# Bridge.net
KiCad netlist of a schematic drawn in Altium Designer
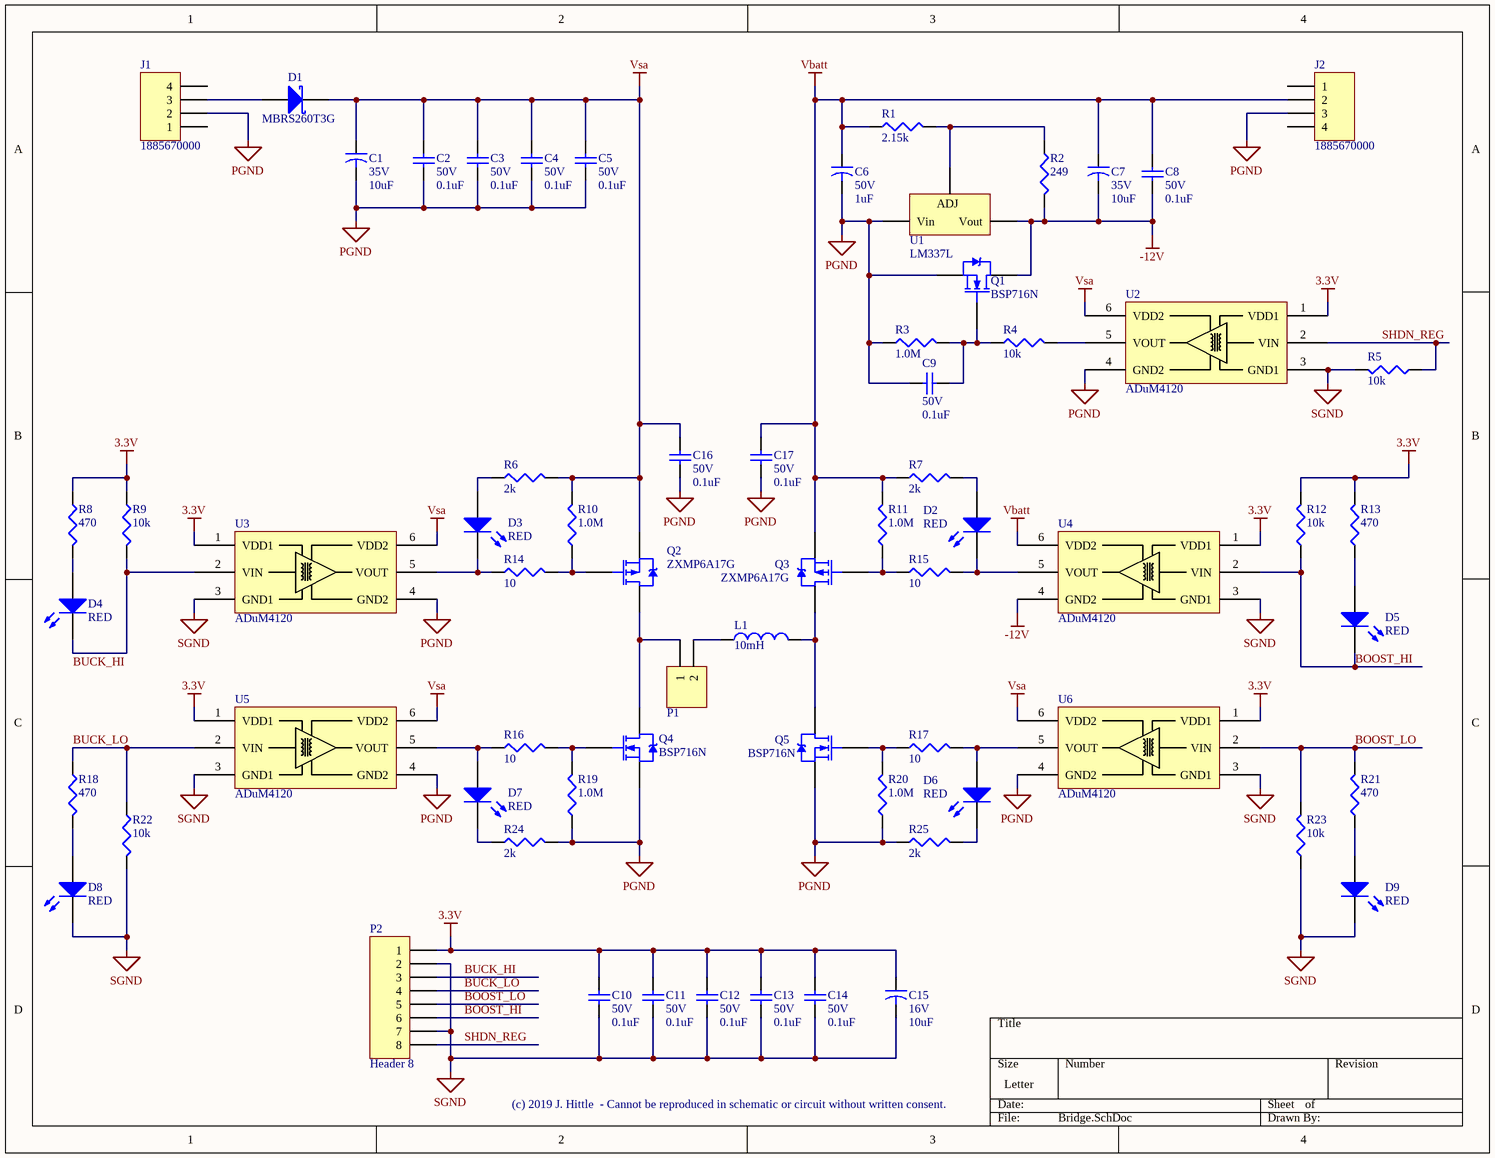
[diagram p0: Bridge.SchDoc]

(export (version "E")
  (design (tool "Eeschema 10.0.6"))
  (components
    (comp (ref "C1")
      (value "10uF")
      (footprint "C2312 Tantalum")
      (description "Capacitor, 600mohm, 200mA@100kHz")
      (fields
        (field (name "PART NUMBER") "TRJC106K035R0600")
        (field (name "VOLTAGE") "35V")
        (field (name "Comment") "Cap Polarized")
      )
      (libsource (lib "Generic Devices") (part "Cap Polarized"))
    )
    (comp (ref "C2")
      (value "0.1uF")
      (footprint "C0805")
      (description "Capacitor")
      (fields
        (field (name "PART NUMBER") "CL21B104KBCNNNC")
        (field (name "VOLTAGE") "50V")
        (field (name "Comment") "Cap Chip")
      )
      (libsource (lib "Generic Devices") (part "Cap Chip"))
    )
    (comp (ref "C3")
      (value "0.1uF")
      (footprint "C0805")
      (description "Capacitor")
      (fields
        (field (name "PART NUMBER") "CL21B104KBCNNNC")
        (field (name "VOLTAGE") "50V")
        (field (name "Comment") "Cap Chip")
      )
      (libsource (lib "Generic Devices") (part "Cap Chip"))
    )
    (comp (ref "C4")
      (value "0.1uF")
      (footprint "C0805")
      (description "Capacitor")
      (fields
        (field (name "PART NUMBER") "CL21B104KBCNNNC")
        (field (name "VOLTAGE") "50V")
        (field (name "Comment") "Cap Chip")
      )
      (libsource (lib "Generic Devices") (part "Cap Chip"))
    )
    (comp (ref "C5")
      (value "0.1uF")
      (footprint "C0805")
      (description "Capacitor")
      (fields
        (field (name "PART NUMBER") "CL21B104KBCNNNC")
        (field (name "VOLTAGE") "50V")
        (field (name "Comment") "Cap Chip")
      )
      (libsource (lib "Generic Devices") (part "Cap Chip"))
    )
    (comp (ref "C6")
      (value "1uF")
      (footprint "C2312 Tantalum")
      (description "Capacitor, 600mohm, 200mA@100kHz")
      (fields
        (field (name "PART NUMBER") "TAJC105K050RNJ")
        (field (name "VOLTAGE") "50V")
        (field (name "Comment") "Cap Polarized")
      )
      (libsource (lib "Generic Devices") (part "Cap Polarized"))
    )
    (comp (ref "C7")
      (value "10uF")
      (footprint "C2312 Tantalum")
      (description "Capacitor, 600mohm, 200mA@100kHz")
      (fields
        (field (name "PART NUMBER") "TRJC106K035R0600")
        (field (name "VOLTAGE") "35V")
        (field (name "Comment") "Cap Polarized")
      )
      (libsource (lib "Generic Devices") (part "Cap Polarized"))
    )
    (comp (ref "C8")
      (value "0.1uF")
      (footprint "C0805")
      (description "Capacitor")
      (fields
        (field (name "PART NUMBER") "CL21B104KBCNNNC")
        (field (name "VOLTAGE") "50V")
        (field (name "Comment") "Cap Chip")
      )
      (libsource (lib "Generic Devices") (part "Cap Chip"))
    )
    (comp (ref "C9")
      (value "0.1uF")
      (footprint "C0603")
      (description "Capacitor")
      (fields
        (field (name "PART NUMBER") "CL10B104KB8NNNC")
        (field (name "VOLTAGE") "50V")
        (field (name "Comment") "Cap Chip")
      )
      (libsource (lib "Generic Devices") (part "Cap Chip"))
    )
    (comp (ref "C10")
      (value "0.1uF")
      (footprint "C0805")
      (description "Capacitor")
      (fields
        (field (name "PART NUMBER") "CL21B104KBCNNNC")
        (field (name "VOLTAGE") "50V")
        (field (name "Comment") "Cap Chip")
      )
      (libsource (lib "Generic Devices") (part "Cap Chip"))
    )
    (comp (ref "C11")
      (value "0.1uF")
      (footprint "C0805")
      (description "Capacitor")
      (fields
        (field (name "PART NUMBER") "CL21B104KBCNNNC")
        (field (name "VOLTAGE") "50V")
        (field (name "Comment") "Cap Chip")
      )
      (libsource (lib "Generic Devices") (part "Cap Chip"))
    )
    (comp (ref "C12")
      (value "0.1uF")
      (footprint "C0805")
      (description "Capacitor")
      (fields
        (field (name "PART NUMBER") "CL21B104KBCNNNC")
        (field (name "VOLTAGE") "50V")
        (field (name "Comment") "Cap Chip")
      )
      (libsource (lib "Generic Devices") (part "Cap Chip"))
    )
    (comp (ref "C13")
      (value "0.1uF")
      (footprint "C0805")
      (description "Capacitor")
      (fields
        (field (name "PART NUMBER") "CL21B104KBCNNNC")
        (field (name "VOLTAGE") "50V")
        (field (name "Comment") "Cap Chip")
      )
      (libsource (lib "Generic Devices") (part "Cap Chip"))
    )
    (comp (ref "C14")
      (value "0.1uF")
      (footprint "C0805")
      (description "Capacitor")
      (fields
        (field (name "PART NUMBER") "CL21B104KBCNNNC")
        (field (name "VOLTAGE") "50V")
        (field (name "Comment") "Cap Chip")
      )
      (libsource (lib "Generic Devices") (part "Cap Chip"))
    )
    (comp (ref "C15")
      (value "10uF")
      (footprint "C1206 Tantalum")
      (description "Capacitor, 600mohm, 200mA@100kHz")
      (fields
        (field (name "PART NUMBER") "TAJA106K016RNJV")
        (field (name "VOLTAGE") "16V")
        (field (name "Comment") "Cap Polarized")
      )
      (libsource (lib "Generic Devices") (part "Cap Polarized"))
    )
    (comp (ref "C16")
      (value "0.1uF")
      (footprint "C0603")
      (description "Capacitor")
      (fields
        (field (name "PART NUMBER") "CL10B104KB8NNNC")
        (field (name "VOLTAGE") "50V")
        (field (name "Comment") "Cap Chip")
      )
      (libsource (lib "Generic Devices") (part "Cap Chip"))
    )
    (comp (ref "C17")
      (value "0.1uF")
      (footprint "C0603")
      (description "Capacitor")
      (fields
        (field (name "PART NUMBER") "CL10B104KB8NNNC")
        (field (name "VOLTAGE") "50V")
        (field (name "Comment") "Cap Chip")
      )
      (libsource (lib "Generic Devices") (part "Cap Chip"))
    )
    (comp (ref "D1")
      (value "MBRS260T3G")
      (footprint "SMB")
      (description "Schottky Diode")
      (fields (field (name "PUBLISHER") "Altium Limited"))
      (libsource (lib "Miscellaneous Devices") (part "D Schottky"))
    )
    (comp (ref "D2")
      (value "RED")
      (footprint "Generic Devices:0603_LED_Red")
      (description "Red LED")
      (fields (field (name "PART NUMBER") "LTST-C193KRKT-5A") (field (name "PUBLISHER") "Altium Limited"))
      (libsource (lib "Miscellaneous Devices") (part "LED0"))
    )
    (comp (ref "D3")
      (value "RED")
      (footprint "Generic Devices:0603_LED_Red")
      (description "Red LED")
      (fields (field (name "PART NUMBER") "LTST-C193KRKT-5A") (field (name "PUBLISHER") "Altium Limited"))
      (libsource (lib "Miscellaneous Devices") (part "LED0"))
    )
    (comp (ref "D4")
      (value "RED")
      (footprint "Generic Devices:0603_LED_Red")
      (description "Red LED")
      (fields (field (name "PART NUMBER") "LTST-C193KRKT-5A") (field (name "PUBLISHER") "Altium Limited"))
      (libsource (lib "Miscellaneous Devices") (part "LED0"))
    )
    (comp (ref "D5")
      (value "RED")
      (footprint "Generic Devices:0603_LED_Red")
      (description "Red LED")
      (fields (field (name "PART NUMBER") "LTST-C193KRKT-5A") (field (name "PUBLISHER") "Altium Limited"))
      (libsource (lib "Miscellaneous Devices") (part "LED0"))
    )
    (comp (ref "D6")
      (value "RED")
      (footprint "Generic Devices:0603_LED_Red")
      (description "Red LED")
      (fields (field (name "PART NUMBER") "LTST-C193KRKT-5A") (field (name "PUBLISHER") "Altium Limited"))
      (libsource (lib "Miscellaneous Devices") (part "LED0"))
    )
    (comp (ref "D7")
      (value "RED")
      (footprint "Generic Devices:0603_LED_Red")
      (description "Red LED")
      (fields (field (name "PART NUMBER") "LTST-C193KRKT-5A") (field (name "PUBLISHER") "Altium Limited"))
      (libsource (lib "Miscellaneous Devices") (part "LED0"))
    )
    (comp (ref "D8")
      (value "RED")
      (footprint "Generic Devices:0603_LED_Red")
      (description "Red LED")
      (fields (field (name "PART NUMBER") "LTST-C193KRKT-5A") (field (name "PUBLISHER") "Altium Limited"))
      (libsource (lib "Miscellaneous Devices") (part "LED0"))
    )
    (comp (ref "D9")
      (value "RED")
      (footprint "Generic Devices:0603_LED_Red")
      (description "Red LED")
      (fields (field (name "PART NUMBER") "LTST-C193KRKT-5A") (field (name "PUBLISHER") "Altium Limited"))
      (libsource (lib "Miscellaneous Devices") (part "LED0"))
    )
    (comp (ref "J1")
      (value "1885670000")
      (footprint "1885670000")
      (description "TERM BLOCK 4POS 45DEG 3.5MM PCB")
      (fields (field (name "VOLTAGE") "300V"))
      (libsource (lib "") (part "1885670000_1"))
    )
    (comp (ref "J2")
      (value "1885670000")
      (footprint "1885670000")
      (description "TERM BLOCK 4POS 45DEG 3.5MM PCB")
      (fields (field (name "VOLTAGE") "300V"))
      (libsource (lib "Connectors") (part "1885670000"))
    )
    (comp (ref "L1")
      (value "10mH")
      (footprint "141060XC")
      (description "Inductor")
      (fields (field (name "PART NUMBER") "1410606C or 1410604C") (field (name "PUBLISHER") "Altium Limited"))
      (libsource (lib "Miscellaneous Devices") (part "Inductor"))
    )
    (comp (ref "P1")
      (value "~")
      (footprint "HDR1X2")
      (description "Header, 2-Pin, 100mil")
      (fields (field (name "PUBLISHER") "Altium Limited"))
      (libsource (lib "Connectors") (part "Header 2"))
    )
    (comp (ref "P2")
      (value "Header 8")
      (footprint "HDR1X8")
      (description "Header, 8-Pin, 100mil")
      (fields (field (name "PUBLISHER") "Altium Limited"))
      (libsource (lib "Miscellaneous Connectors") (part "Header 8"))
    )
    (comp (ref "Q1")
      (value "BSP716N")
      (footprint "SOT223")
      (description "N-Channel MOSFET")
      (fields (field (name "PART NUMBER") "BSP716NH6327XTSA1"))
      (libsource (lib "Generic Devices") (part "NMOS"))
    )
    (comp (ref "Q2")
      (value "ZXMP6A17G")
      (footprint "SOT223")
      (description "P-Channel MOSFET")
      (fields (field (name "PART NUMBER") "ZXMP6A17GTA"))
      (libsource (lib "Generic Devices") (part "PMOS"))
    )
    (comp (ref "Q3")
      (value "ZXMP6A17G")
      (footprint "SOT223")
      (description "P-Channel MOSFET")
      (fields (field (name "PART NUMBER") "ZXMP6A17GTA"))
      (libsource (lib "Generic Devices") (part "PMOS"))
    )
    (comp (ref "Q4")
      (value "BSP716N")
      (footprint "SOT223")
      (description "N-Channel MOSFET")
      (fields (field (name "PART NUMBER") "BSP716NH6327XTSA1"))
      (libsource (lib "Generic Devices") (part "NMOS"))
    )
    (comp (ref "Q5")
      (value "BSP716N")
      (footprint "SOT223")
      (description "N-Channel MOSFET")
      (fields (field (name "PART NUMBER") "BSP716NH6327XTSA1"))
      (libsource (lib "Generic Devices") (part "NMOS"))
    )
    (comp (ref "R1")
      (value "2.15k")
      (footprint "R0805")
      (description "Resistor")
      (fields (field (name "PART NUMBER") "RC0805FR-072K15L") (field (name "POWER") "0.125"))
      (libsource (lib "Generic Devices") (part "Resistor_Chip"))
    )
    (comp (ref "R2")
      (value "249")
      (footprint "R0603")
      (description "Resistor")
      (fields (field (name "PART NUMBER") "RC0603FR-07249RL") (field (name "POWER") "0.100"))
      (libsource (lib "Generic Devices") (part "Resistor_Chip"))
    )
    (comp (ref "R3")
      (value "1.0M")
      (footprint "R0603")
      (description "Resistor")
      (fields (field (name "PART NUMBER") "RC0603FR-071ML") (field (name "POWER") "0.100"))
      (libsource (lib "Generic Devices") (part "Resistor_Chip"))
    )
    (comp (ref "R4")
      (value "10k")
      (footprint "R0603")
      (description "Resistor")
      (fields (field (name "PART NUMBER") "RC0603FR-0710KL") (field (name "POWER") "0.100"))
      (libsource (lib "Generic Devices") (part "Resistor_Chip"))
    )
    (comp (ref "R5")
      (value "10k")
      (footprint "R0603")
      (description "Resistor")
      (fields (field (name "PART NUMBER") "RC0603FR-0710KL") (field (name "POWER") "0.100"))
      (libsource (lib "Generic Devices") (part "Resistor_Chip"))
    )
    (comp (ref "R6")
      (value "2k")
      (footprint "R0603")
      (description "Resistor")
      (fields (field (name "PART NUMBER") "RC0805FR-072KL") (field (name "POWER") "0.125"))
      (libsource (lib "Generic Devices") (part "Resistor_Chip"))
    )
    (comp (ref "R7")
      (value "2k")
      (footprint "R0603")
      (description "Resistor")
      (fields (field (name "PART NUMBER") "RC0805FR-072KL") (field (name "POWER") "0.125"))
      (libsource (lib "Generic Devices") (part "Resistor_Chip"))
    )
    (comp (ref "R8")
      (value "470")
      (footprint "R0603")
      (description "Resistor")
      (fields (field (name "PART NUMBER") "RC0603FR-07470RL") (field (name "POWER") "0.100"))
      (libsource (lib "Generic Devices") (part "Resistor_Chip"))
    )
    (comp (ref "R9")
      (value "10k")
      (footprint "R0603")
      (description "Resistor")
      (fields (field (name "PART NUMBER") "RC0603FR-0710KL") (field (name "POWER") "0.100"))
      (libsource (lib "Generic Devices") (part "Resistor_Chip"))
    )
    (comp (ref "R10")
      (value "1.0M")
      (footprint "R0603")
      (description "Resistor")
      (fields (field (name "PART NUMBER") "RC0603FR-071ML") (field (name "POWER") "0.100"))
      (libsource (lib "Generic Devices") (part "Resistor_Chip"))
    )
    (comp (ref "R11")
      (value "1.0M")
      (footprint "R0603")
      (description "Resistor")
      (fields (field (name "PART NUMBER") "RC0603FR-071ML") (field (name "POWER") "0.100"))
      (libsource (lib "Generic Devices") (part "Resistor_Chip"))
    )
    (comp (ref "R12")
      (value "10k")
      (footprint "R0603")
      (description "Resistor")
      (fields (field (name "PART NUMBER") "RC0603FR-0710KL") (field (name "POWER") "0.100"))
      (libsource (lib "Generic Devices") (part "Resistor_Chip"))
    )
    (comp (ref "R13")
      (value "470")
      (footprint "R0603")
      (description "Resistor")
      (fields (field (name "PART NUMBER") "RC0603FR-07470RL") (field (name "POWER") "0.100"))
      (libsource (lib "Generic Devices") (part "Resistor_Chip"))
    )
    (comp (ref "R14")
      (value "10")
      (footprint "R1206")
      (description "Resistor")
      (fields (field (name "PART NUMBER") "RC1206FR-0710RL") (field (name "POWER") "0.250"))
      (libsource (lib "Generic Devices") (part "Resistor_Chip"))
    )
    (comp (ref "R15")
      (value "10")
      (footprint "R1206")
      (description "Resistor")
      (fields (field (name "PART NUMBER") "RC1206FR-0710RL") (field (name "POWER") "0.250"))
      (libsource (lib "Generic Devices") (part "Resistor_Chip"))
    )
    (comp (ref "R16")
      (value "10")
      (footprint "R1206")
      (description "Resistor")
      (fields (field (name "PART NUMBER") "RC1206FR-0710RL") (field (name "POWER") "0.250"))
      (libsource (lib "Generic Devices") (part "Resistor_Chip"))
    )
    (comp (ref "R17")
      (value "10")
      (footprint "R1206")
      (description "Resistor")
      (fields (field (name "PART NUMBER") "RC1206FR-0710RL") (field (name "POWER") "0.250"))
      (libsource (lib "Generic Devices") (part "Resistor_Chip"))
    )
    (comp (ref "R18")
      (value "470")
      (footprint "R0603")
      (description "Resistor")
      (fields (field (name "PART NUMBER") "RC0603FR-07470RL") (field (name "POWER") "0.100"))
      (libsource (lib "Generic Devices") (part "Resistor_Chip"))
    )
    (comp (ref "R19")
      (value "1.0M")
      (footprint "R0603")
      (description "Resistor")
      (fields (field (name "PART NUMBER") "RC0603FR-071ML") (field (name "POWER") "0.100"))
      (libsource (lib "Generic Devices") (part "Resistor_Chip"))
    )
    (comp (ref "R20")
      (value "1.0M")
      (footprint "R0603")
      (description "Resistor")
      (fields (field (name "PART NUMBER") "RC0603FR-071ML") (field (name "POWER") "0.100"))
      (libsource (lib "Generic Devices") (part "Resistor_Chip"))
    )
    (comp (ref "R21")
      (value "470")
      (footprint "R0603")
      (description "Resistor")
      (fields (field (name "PART NUMBER") "RC0603FR-07470RL") (field (name "POWER") "0.100"))
      (libsource (lib "Generic Devices") (part "Resistor_Chip"))
    )
    (comp (ref "R22")
      (value "10k")
      (footprint "R0603")
      (description "Resistor")
      (fields (field (name "PART NUMBER") "RC0603FR-0710KL") (field (name "POWER") "0.100"))
      (libsource (lib "Generic Devices") (part "Resistor_Chip"))
    )
    (comp (ref "R23")
      (value "10k")
      (footprint "R0603")
      (description "Resistor")
      (fields (field (name "PART NUMBER") "RC0603FR-0710KL") (field (name "POWER") "0.100"))
      (libsource (lib "Generic Devices") (part "Resistor_Chip"))
    )
    (comp (ref "R24")
      (value "2k")
      (footprint "R0603")
      (description "Resistor")
      (fields (field (name "PART NUMBER") "RC0805FR-072KL") (field (name "POWER") "0.125"))
      (libsource (lib "Generic Devices") (part "Resistor_Chip"))
    )
    (comp (ref "R25")
      (value "2k")
      (footprint "R0603")
      (description "Resistor")
      (fields (field (name "PART NUMBER") "RC0805FR-072KL") (field (name "POWER") "0.125"))
      (libsource (lib "Generic Devices") (part "Resistor_Chip"))
    )
    (comp (ref "U1")
      (value "LM337L")
      (footprint "TO-92A")
      (description "Negative Voltage Regulator")
      (fields (field (name "PART NUMBER") "LM337LZ/NOPB"))
      (libsource (lib "Generic Devices") (part "Neg Volt Reg - Adj"))
    )
    (comp (ref "U2")
      (value "ADuM4120")
      (footprint "SOIC RI-6-1")
      (description "Isolated Gate-Driver")
      (fields (field (name "PART NUMBER") "ADuM4120-1ARIZ"))
      (libsource (lib "Specific Devices") (part "ADuM4120"))
    )
    (comp (ref "U3")
      (value "ADuM4120")
      (footprint "SOIC RI-6-1")
      (description "Isolated Gate-Driver")
      (fields (field (name "PART NUMBER") "ADuM4120-1ARIZ"))
      (libsource (lib "") (part "ADuM4120_1"))
    )
    (comp (ref "U4")
      (value "ADuM4120")
      (footprint "SOIC RI-6-1")
      (description "Isolated Gate-Driver")
      (fields (field (name "PART NUMBER") "ADuM4120-1ARIZ"))
      (libsource (lib "Specific Devices") (part "ADuM4120"))
    )
    (comp (ref "U5")
      (value "ADuM4120")
      (footprint "SOIC RI-6-1")
      (description "Isolated Gate-Driver")
      (fields (field (name "PART NUMBER") "ADuM4120-1ARIZ"))
      (libsource (lib "") (part "ADuM4120_1"))
    )
    (comp (ref "U6")
      (value "ADuM4120")
      (footprint "SOIC RI-6-1")
      (description "Isolated Gate-Driver")
      (fields (field (name "PART NUMBER") "ADuM4120-1ARIZ"))
      (libsource (lib "Specific Devices") (part "ADuM4120"))
    )
  )
  (nets
    (net (code "1") (name "-12V") (class "Default")
      (node (ref "C7") (pin "2") (pinfunction "2_2") (pintype "passive"))
      (node (ref "C8") (pin "1") (pinfunction "1_1") (pintype "passive"))
      (node (ref "Q1") (pin "D") (pinfunction "D_D") (pintype "passive"))
      (node (ref "R2") (pin "2") (pinfunction "2_2") (pintype "passive"))
      (node (ref "U1") (pin "Vout") (pinfunction "Vout_Vout") (pintype "passive"))
      (node (ref "U4") (pin "4") (pinfunction "GND2_4") (pintype "passive"))
    )
    (net (code "2") (name "/BOOST_HI") (class "Default")
      (node (ref "D5") (pin "2") (pinfunction "K_2") (pintype "passive"))
      (node (ref "P2") (pin "6") (pinfunction "6_6") (pintype "passive"))
      (node (ref "R12") (pin "1") (pinfunction "1_1") (pintype "passive"))
      (node (ref "U4") (pin "2") (pinfunction "VIN_2") (pintype "passive"))
    )
    (net (code "3") (name "/BOOST_LO") (class "Default")
      (node (ref "P2") (pin "5") (pinfunction "5_5") (pintype "passive"))
      (node (ref "R21") (pin "2") (pinfunction "2_2") (pintype "passive"))
      (node (ref "R23") (pin "2") (pinfunction "2_2") (pintype "passive"))
      (node (ref "U6") (pin "2") (pinfunction "VIN_2") (pintype "passive"))
    )
    (net (code "4") (name "/BUCK_HI") (class "Default")
      (node (ref "D4") (pin "2") (pinfunction "K_2") (pintype "passive"))
      (node (ref "P2") (pin "3") (pinfunction "3_3") (pintype "passive"))
      (node (ref "R9") (pin "1") (pinfunction "1_1") (pintype "passive"))
      (node (ref "U3") (pin "2") (pinfunction "VIN_2") (pintype "passive"))
    )
    (net (code "5") (name "/BUCK_LO") (class "Default")
      (node (ref "P2") (pin "4") (pinfunction "4_4") (pintype "passive"))
      (node (ref "R18") (pin "2") (pinfunction "2_2") (pintype "passive"))
      (node (ref "R22") (pin "2") (pinfunction "2_2") (pintype "passive"))
      (node (ref "U5") (pin "2") (pinfunction "VIN_2") (pintype "passive"))
    )
    (net (code "6") (name "/SHDN_REG") (class "Default")
      (node (ref "P2") (pin "8") (pinfunction "8_8") (pintype "passive"))
      (node (ref "R5") (pin "1") (pinfunction "1_1") (pintype "passive"))
      (node (ref "U2") (pin "2") (pinfunction "VIN_2") (pintype "passive"))
    )
    (net (code "7") (name "3.3V") (class "Default")
      (node (ref "C10") (pin "2") (pinfunction "2_2") (pintype "passive"))
      (node (ref "C11") (pin "2") (pinfunction "2_2") (pintype "passive"))
      (node (ref "C12") (pin "2") (pinfunction "2_2") (pintype "passive"))
      (node (ref "C13") (pin "2") (pinfunction "2_2") (pintype "passive"))
      (node (ref "C14") (pin "2") (pinfunction "2_2") (pintype "passive"))
      (node (ref "C15") (pin "1") (pinfunction "1_1") (pintype "passive"))
      (node (ref "P2") (pin "1") (pinfunction "1_1") (pintype "passive"))
      (node (ref "R12") (pin "2") (pinfunction "2_2") (pintype "passive"))
      (node (ref "R13") (pin "2") (pinfunction "2_2") (pintype "passive"))
      (node (ref "R8") (pin "2") (pinfunction "2_2") (pintype "passive"))
      (node (ref "R9") (pin "2") (pinfunction "2_2") (pintype "passive"))
      (node (ref "U2") (pin "1") (pinfunction "VDD1_1") (pintype "passive"))
      (node (ref "U3") (pin "1") (pinfunction "VDD1_1") (pintype "passive"))
      (node (ref "U4") (pin "1") (pinfunction "VDD1_1") (pintype "passive"))
      (node (ref "U5") (pin "1") (pinfunction "VDD1_1") (pintype "passive"))
      (node (ref "U6") (pin "1") (pinfunction "VDD1_1") (pintype "passive"))
    )
    (net (code "8") (name "Net-(C9-Pad1)") (class "Default")
      (node (ref "C9") (pin "1") (pinfunction "1_1") (pintype "passive"))
      (node (ref "Q1") (pin "G") (pinfunction "G_G") (pintype "passive"))
      (node (ref "R3") (pin "2") (pinfunction "2_2") (pintype "passive"))
      (node (ref "R4") (pin "1") (pinfunction "1_1") (pintype "passive"))
    )
    (net (code "9") (name "Net-(D1-A)") (class "Default")
      (node (ref "D1") (pin "1") (pinfunction "A_1") (pintype "passive"))
      (node (ref "J1") (pin "3") (pinfunction "3_3") (pintype "passive"))
    )
    (net (code "10") (name "Net-(D2-A)") (class "Default")
      (node (ref "D2") (pin "1") (pinfunction "A_1") (pintype "passive"))
      (node (ref "R7") (pin "2") (pinfunction "2_2") (pintype "passive"))
    )
    (net (code "11") (name "Net-(D2-K)") (class "Default")
      (node (ref "D2") (pin "2") (pinfunction "K_2") (pintype "passive"))
      (node (ref "R15") (pin "2") (pinfunction "2_2") (pintype "passive"))
      (node (ref "U4") (pin "5") (pinfunction "VOUT_5") (pintype "passive"))
    )
    (net (code "12") (name "Net-(D3-A)") (class "Default")
      (node (ref "D3") (pin "1") (pinfunction "A_1") (pintype "passive"))
      (node (ref "R6") (pin "2") (pinfunction "2_2") (pintype "passive"))
    )
    (net (code "13") (name "Net-(D3-K)") (class "Default")
      (node (ref "D3") (pin "2") (pinfunction "K_2") (pintype "passive"))
      (node (ref "R14") (pin "1") (pinfunction "1_1") (pintype "passive"))
      (node (ref "U3") (pin "5") (pinfunction "VOUT_5") (pintype "passive"))
    )
    (net (code "14") (name "Net-(D4-A)") (class "Default")
      (node (ref "D4") (pin "1") (pinfunction "A_1") (pintype "passive"))
      (node (ref "R8") (pin "1") (pinfunction "1_1") (pintype "passive"))
    )
    (net (code "15") (name "Net-(D5-A)") (class "Default")
      (node (ref "D5") (pin "1") (pinfunction "A_1") (pintype "passive"))
      (node (ref "R13") (pin "1") (pinfunction "1_1") (pintype "passive"))
    )
    (net (code "16") (name "Net-(D6-A)") (class "Default")
      (node (ref "D6") (pin "1") (pinfunction "A_1") (pintype "passive"))
      (node (ref "R17") (pin "2") (pinfunction "2_2") (pintype "passive"))
      (node (ref "U6") (pin "5") (pinfunction "VOUT_5") (pintype "passive"))
    )
    (net (code "17") (name "Net-(D6-K)") (class "Default")
      (node (ref "D6") (pin "2") (pinfunction "K_2") (pintype "passive"))
      (node (ref "R25") (pin "2") (pinfunction "2_2") (pintype "passive"))
    )
    (net (code "18") (name "Net-(D7-A)") (class "Default")
      (node (ref "D7") (pin "1") (pinfunction "A_1") (pintype "passive"))
      (node (ref "R16") (pin "1") (pinfunction "1_1") (pintype "passive"))
      (node (ref "U5") (pin "5") (pinfunction "VOUT_5") (pintype "passive"))
    )
    (net (code "19") (name "Net-(D7-K)") (class "Default")
      (node (ref "D7") (pin "2") (pinfunction "K_2") (pintype "passive"))
      (node (ref "R24") (pin "1") (pinfunction "1_1") (pintype "passive"))
    )
    (net (code "20") (name "Net-(D8-A)") (class "Default")
      (node (ref "D8") (pin "1") (pinfunction "A_1") (pintype "passive"))
      (node (ref "R18") (pin "1") (pinfunction "1_1") (pintype "passive"))
    )
    (net (code "21") (name "Net-(D9-A)") (class "Default")
      (node (ref "D9") (pin "1") (pinfunction "A_1") (pintype "passive"))
      (node (ref "R21") (pin "1") (pinfunction "1_1") (pintype "passive"))
    )
    (net (code "22") (name "Net-(L1-Pad1)") (class "Default")
      (node (ref "L1") (pin "1") (pinfunction "1_1") (pintype "passive"))
      (node (ref "P1") (pin "2") (pinfunction "2_2") (pintype "passive"))
    )
    (net (code "23") (name "Net-(L1-Pad2)") (class "Default")
      (node (ref "L1") (pin "2") (pinfunction "2_2") (pintype "passive"))
      (node (ref "Q3") (pin "D") (pinfunction "D_D") (pintype "passive"))
      (node (ref "Q5") (pin "D") (pinfunction "D_D") (pintype "passive"))
    )
    (net (code "24") (name "Net-(P1-Pad1)") (class "Default")
      (node (ref "P1") (pin "1") (pinfunction "1_1") (pintype "passive"))
      (node (ref "Q2") (pin "D") (pinfunction "D_D") (pintype "passive"))
      (node (ref "Q4") (pin "D") (pinfunction "D_D") (pintype "passive"))
    )
    (net (code "25") (name "Net-(Q2-PadG)") (class "Default")
      (node (ref "Q2") (pin "G") (pinfunction "G_G") (pintype "passive"))
      (node (ref "R10") (pin "1") (pinfunction "1_1") (pintype "passive"))
      (node (ref "R14") (pin "2") (pinfunction "2_2") (pintype "passive"))
    )
    (net (code "26") (name "Net-(Q3-PadG)") (class "Default")
      (node (ref "Q3") (pin "G") (pinfunction "G_G") (pintype "passive"))
      (node (ref "R11") (pin "1") (pinfunction "1_1") (pintype "passive"))
      (node (ref "R15") (pin "1") (pinfunction "1_1") (pintype "passive"))
    )
    (net (code "27") (name "Net-(Q4-PadG)") (class "Default")
      (node (ref "Q4") (pin "G") (pinfunction "G_G") (pintype "passive"))
      (node (ref "R16") (pin "2") (pinfunction "2_2") (pintype "passive"))
      (node (ref "R19") (pin "2") (pinfunction "2_2") (pintype "passive"))
    )
    (net (code "28") (name "Net-(Q5-PadG)") (class "Default")
      (node (ref "Q5") (pin "G") (pinfunction "G_G") (pintype "passive"))
      (node (ref "R17") (pin "1") (pinfunction "1_1") (pintype "passive"))
      (node (ref "R20") (pin "2") (pinfunction "2_2") (pintype "passive"))
    )
    (net (code "29") (name "Net-(R1-Pad2)") (class "Default")
      (node (ref "R1") (pin "2") (pinfunction "2_2") (pintype "passive"))
      (node (ref "R2") (pin "1") (pinfunction "1_1") (pintype "passive"))
      (node (ref "U1") (pin "GND") (pinfunction "GND_GND") (pintype "passive"))
    )
    (net (code "30") (name "Net-(U2-VOUT)") (class "Default")
      (node (ref "R4") (pin "2") (pinfunction "2_2") (pintype "passive"))
      (node (ref "U2") (pin "5") (pinfunction "VOUT_5") (pintype "passive"))
    )
    (net (code "31") (name "PGND") (class "Default")
      (node (ref "C1") (pin "2") (pinfunction "2_2") (pintype "passive"))
      (node (ref "C16") (pin "1") (pinfunction "1_1") (pintype "passive"))
      (node (ref "C17") (pin "1") (pinfunction "1_1") (pintype "passive"))
      (node (ref "C2") (pin "1") (pinfunction "1_1") (pintype "passive"))
      (node (ref "C3") (pin "1") (pinfunction "1_1") (pintype "passive"))
      (node (ref "C4") (pin "1") (pinfunction "1_1") (pintype "passive"))
      (node (ref "C5") (pin "1") (pinfunction "1_1") (pintype "passive"))
      (node (ref "C6") (pin "2") (pinfunction "2_2") (pintype "passive"))
      (node (ref "C9") (pin "2") (pinfunction "2_2") (pintype "passive"))
      (node (ref "J1") (pin "2") (pinfunction "2_2") (pintype "passive"))
      (node (ref "J2") (pin "3") (pinfunction "3_3") (pintype "passive"))
      (node (ref "Q1") (pin "S") (pinfunction "S_S") (pintype "passive"))
      (node (ref "Q4") (pin "S") (pinfunction "S_S") (pintype "passive"))
      (node (ref "Q5") (pin "S") (pinfunction "S_S") (pintype "passive"))
      (node (ref "R19") (pin "1") (pinfunction "1_1") (pintype "passive"))
      (node (ref "R20") (pin "1") (pinfunction "1_1") (pintype "passive"))
      (node (ref "R24") (pin "2") (pinfunction "2_2") (pintype "passive"))
      (node (ref "R25") (pin "1") (pinfunction "1_1") (pintype "passive"))
      (node (ref "R3") (pin "1") (pinfunction "1_1") (pintype "passive"))
      (node (ref "U1") (pin "Vin") (pinfunction "Vin_Vin") (pintype "passive"))
      (node (ref "U2") (pin "4") (pinfunction "GND2_4") (pintype "passive"))
      (node (ref "U3") (pin "4") (pinfunction "GND2_4") (pintype "passive"))
      (node (ref "U5") (pin "4") (pinfunction "GND2_4") (pintype "passive"))
      (node (ref "U6") (pin "4") (pinfunction "GND2_4") (pintype "passive"))
    )
    (net (code "32") (name "SGND") (class "Default")
      (node (ref "C10") (pin "1") (pinfunction "1_1") (pintype "passive"))
      (node (ref "C11") (pin "1") (pinfunction "1_1") (pintype "passive"))
      (node (ref "C12") (pin "1") (pinfunction "1_1") (pintype "passive"))
      (node (ref "C13") (pin "1") (pinfunction "1_1") (pintype "passive"))
      (node (ref "C14") (pin "1") (pinfunction "1_1") (pintype "passive"))
      (node (ref "C15") (pin "2") (pinfunction "2_2") (pintype "passive"))
      (node (ref "D8") (pin "2") (pinfunction "K_2") (pintype "passive"))
      (node (ref "D9") (pin "2") (pinfunction "K_2") (pintype "passive"))
      (node (ref "P2") (pin "2") (pinfunction "2_2") (pintype "passive"))
      (node (ref "P2") (pin "7") (pinfunction "7_7") (pintype "passive"))
      (node (ref "R22") (pin "1") (pinfunction "1_1") (pintype "passive"))
      (node (ref "R23") (pin "1") (pinfunction "1_1") (pintype "passive"))
      (node (ref "R5") (pin "2") (pinfunction "2_2") (pintype "passive"))
      (node (ref "U2") (pin "3") (pinfunction "GND1_3") (pintype "passive"))
      (node (ref "U3") (pin "3") (pinfunction "GND1_3") (pintype "passive"))
      (node (ref "U4") (pin "3") (pinfunction "GND1_3") (pintype "passive"))
      (node (ref "U5") (pin "3") (pinfunction "GND1_3") (pintype "passive"))
      (node (ref "U6") (pin "3") (pinfunction "GND1_3") (pintype "passive"))
    )
    (net (code "33") (name "Vbatt") (class "Default")
      (node (ref "C17") (pin "2") (pinfunction "2_2") (pintype "passive"))
      (node (ref "C6") (pin "1") (pinfunction "1_1") (pintype "passive"))
      (node (ref "C7") (pin "1") (pinfunction "1_1") (pintype "passive"))
      (node (ref "C8") (pin "2") (pinfunction "2_2") (pintype "passive"))
      (node (ref "J2") (pin "2") (pinfunction "2_2") (pintype "passive"))
      (node (ref "Q3") (pin "S") (pinfunction "S_S") (pintype "passive"))
      (node (ref "R1") (pin "1") (pinfunction "1_1") (pintype "passive"))
      (node (ref "R11") (pin "2") (pinfunction "2_2") (pintype "passive"))
      (node (ref "R7") (pin "1") (pinfunction "1_1") (pintype "passive"))
      (node (ref "U4") (pin "6") (pinfunction "VDD2_6") (pintype "passive"))
    )
    (net (code "34") (name "Vsa") (class "Default")
      (node (ref "C1") (pin "1") (pinfunction "1_1") (pintype "passive"))
      (node (ref "C16") (pin "2") (pinfunction "2_2") (pintype "passive"))
      (node (ref "C2") (pin "2") (pinfunction "2_2") (pintype "passive"))
      (node (ref "C3") (pin "2") (pinfunction "2_2") (pintype "passive"))
      (node (ref "C4") (pin "2") (pinfunction "2_2") (pintype "passive"))
      (node (ref "C5") (pin "2") (pinfunction "2_2") (pintype "passive"))
      (node (ref "D1") (pin "2") (pinfunction "K_2") (pintype "passive"))
      (node (ref "Q2") (pin "S") (pinfunction "S_S") (pintype "passive"))
      (node (ref "R10") (pin "2") (pinfunction "2_2") (pintype "passive"))
      (node (ref "R6") (pin "1") (pinfunction "1_1") (pintype "passive"))
      (node (ref "U2") (pin "6") (pinfunction "VDD2_6") (pintype "passive"))
      (node (ref "U3") (pin "6") (pinfunction "VDD2_6") (pintype "passive"))
      (node (ref "U5") (pin "6") (pinfunction "VDD2_6") (pintype "passive"))
      (node (ref "U6") (pin "6") (pinfunction "VDD2_6") (pintype "passive"))
    )
    (net (code "35") (name "unconnected-(J1-Pad1)") (class "Default")
      (node (ref "J1") (pin "1") (pinfunction "1_1") (pintype "passive"))
    )
    (net (code "36") (name "unconnected-(J1-Pad4)") (class "Default")
      (node (ref "J1") (pin "4") (pinfunction "4_4") (pintype "passive"))
    )
    (net (code "37") (name "unconnected-(J2-Pad1)") (class "Default")
      (node (ref "J2") (pin "1") (pinfunction "1_1") (pintype "passive"))
    )
    (net (code "38") (name "unconnected-(J2-Pad4)") (class "Default")
      (node (ref "J2") (pin "4") (pinfunction "4_4") (pintype "passive"))
    )
  )
)
